# 2012_AVR.net
KiCad netlist of a schematic drawn in Altium Designer
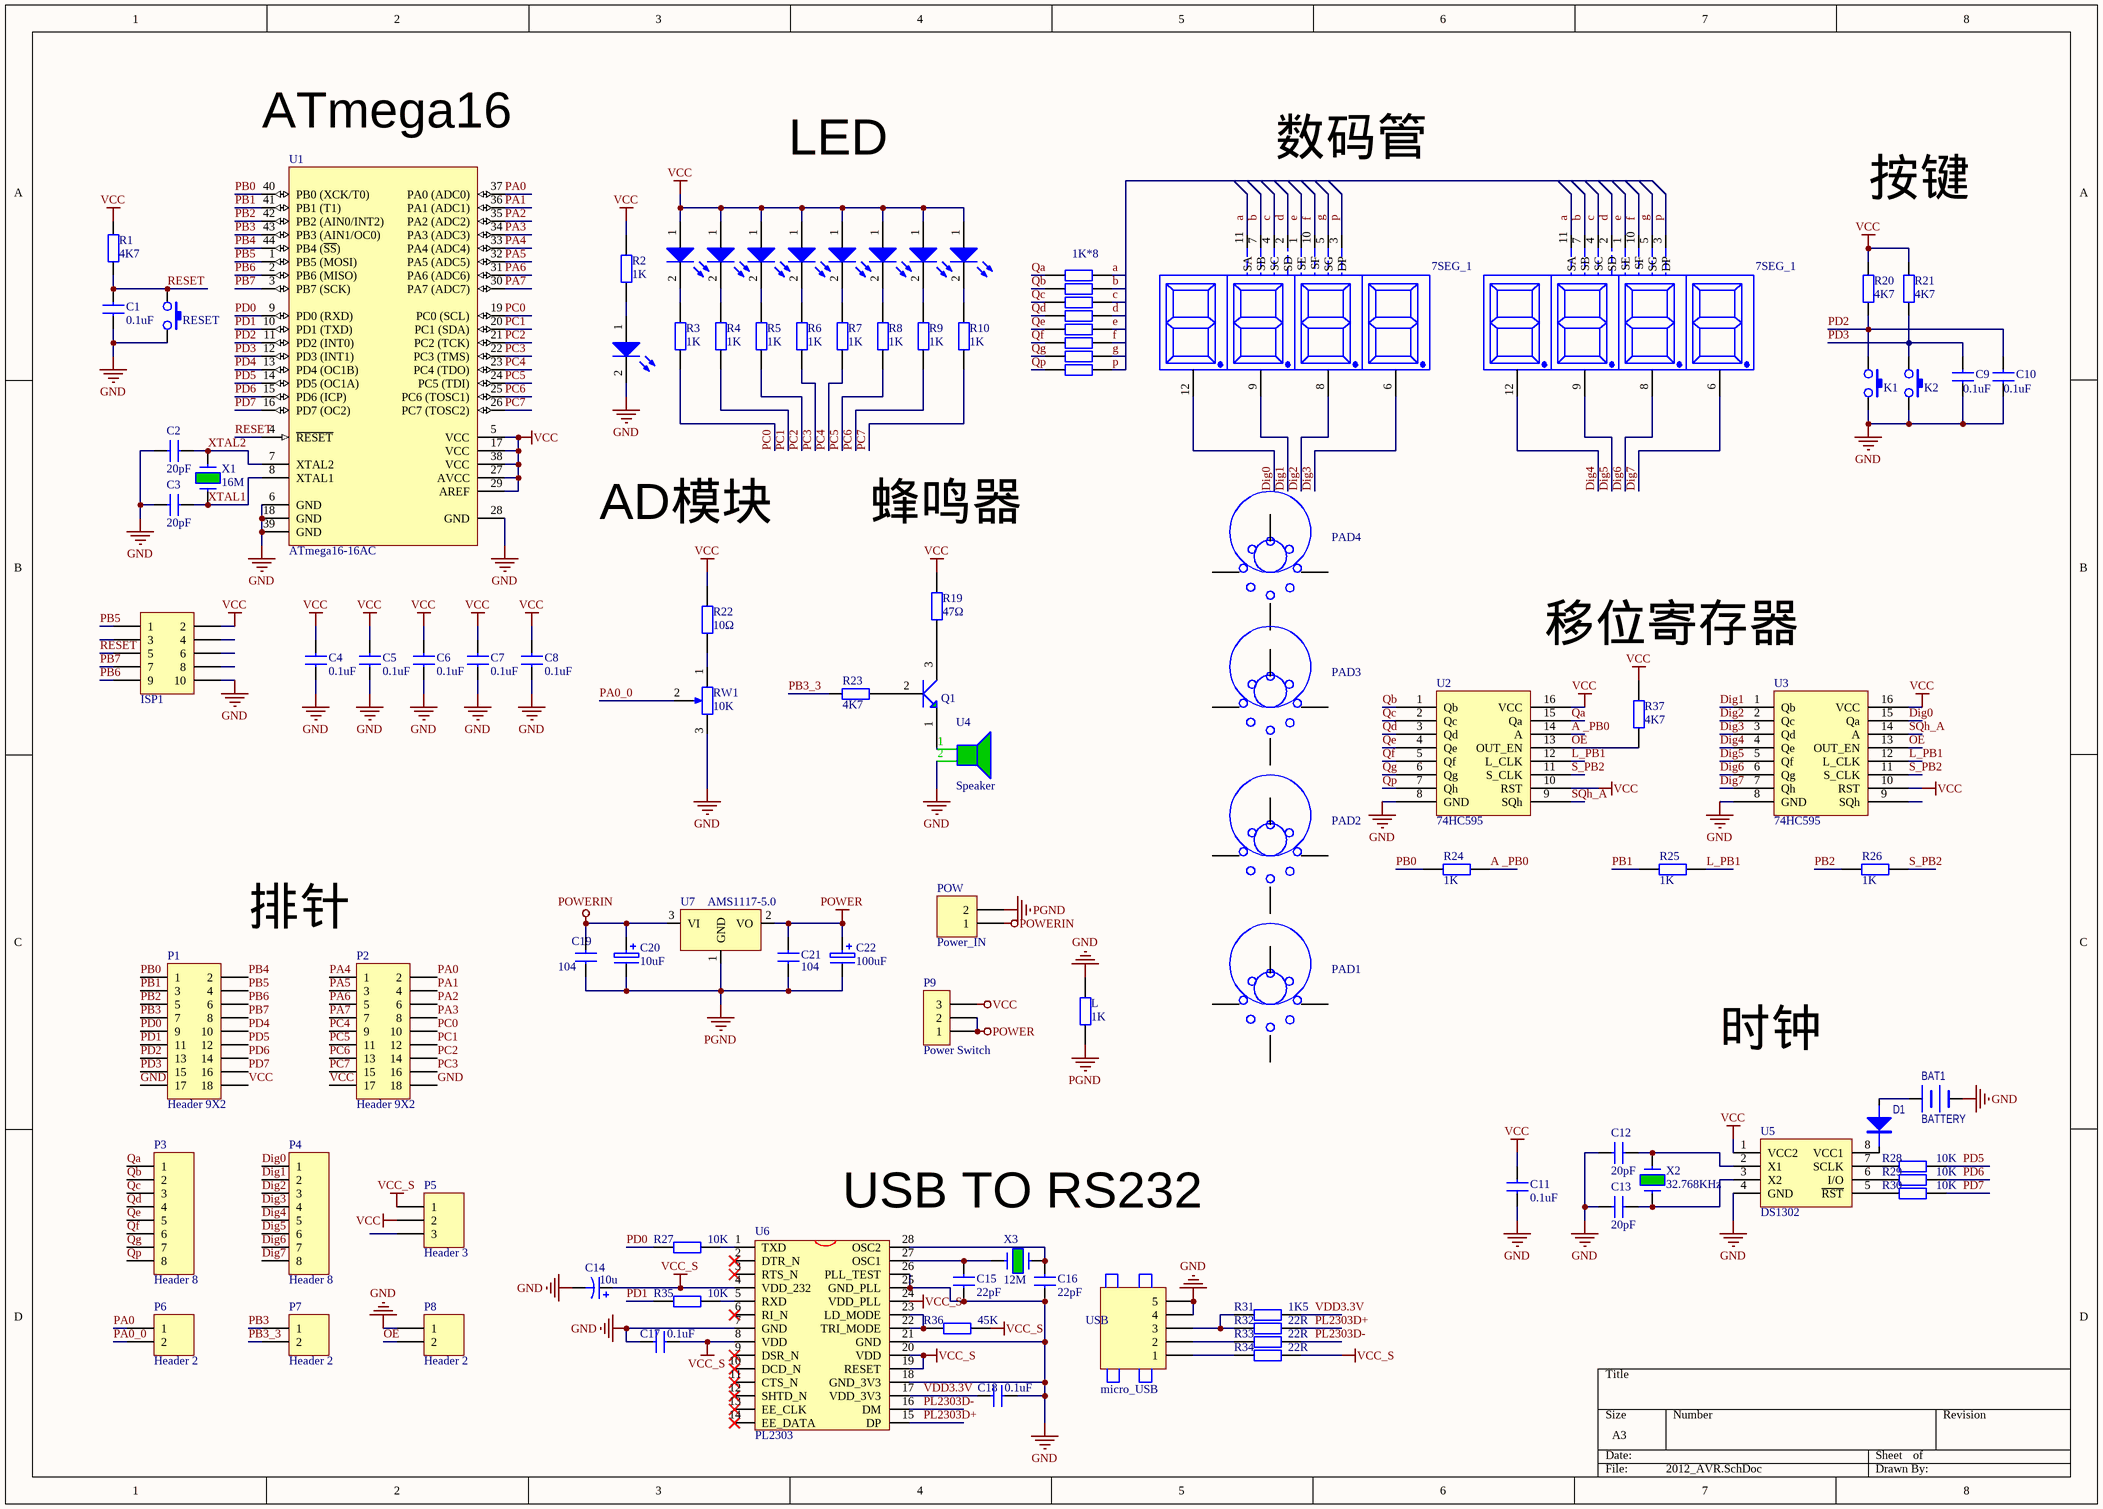
[diagram p0: 2012_AVR.SchDoc]

(export (version "E")
  (design (tool "Eeschema 10.0.6"))
  (components
    (comp (ref "1") (value "7SEG_1") (footprint "DSP-4") (libsource (lib "Free Documents") (part "四位共阴数码管")))
    (comp (ref "2") (value "7SEG_1") (footprint "DSP-4") (libsource (lib "Free Documents") (part "四位共阴数码管")))
    (comp (ref "BAT1")
      (value "BATTERY")
      (footprint "BAT600")
      (libsource (lib "Free Documents") (part "BATTERY"))
    )
    (comp (ref "C1")
      (value "0.1uF")
      (footprint "C0704")
      (description "Capacitor")
      (libsource (lib "Free Documents") (part "CAP"))
    )
    (comp (ref "C2")
      (value "20pF")
      (footprint "C0704")
      (description "Capacitor")
      (libsource (lib "Free Documents") (part "CAP"))
    )
    (comp (ref "C3")
      (value "20pF")
      (footprint "C0704")
      (description "Capacitor")
      (libsource (lib "Free Documents") (part "CAP"))
    )
    (comp (ref "C4")
      (value "0.1uF")
      (footprint "C0704")
      (description "Capacitor")
      (libsource (lib "Free Documents") (part "CAP"))
    )
    (comp (ref "C5")
      (value "0.1uF")
      (footprint "C0704")
      (description "Capacitor")
      (libsource (lib "Free Documents") (part "CAP"))
    )
    (comp (ref "C6")
      (value "0.1uF")
      (footprint "C0704")
      (description "Capacitor")
      (libsource (lib "Free Documents") (part "CAP"))
    )
    (comp (ref "C7")
      (value "0.1uF")
      (footprint "C0704")
      (description "Capacitor")
      (libsource (lib "Free Documents") (part "CAP"))
    )
    (comp (ref "C8")
      (value "0.1uF")
      (footprint "C0704")
      (description "Capacitor")
      (libsource (lib "Free Documents") (part "CAP"))
    )
    (comp (ref "C9")
      (value "0.1uF")
      (footprint "C0704")
      (description "Capacitor")
      (libsource (lib "Free Documents") (part "CAP"))
    )
    (comp (ref "C10")
      (value "0.1uF")
      (footprint "C0704")
      (description "Capacitor")
      (libsource (lib "Free Documents") (part "CAP"))
    )
    (comp (ref "C11")
      (value "0.1uF")
      (footprint "C0704")
      (description "Capacitor")
      (libsource (lib "Free Documents") (part "CAP"))
    )
    (comp (ref "C12")
      (value "20pF")
      (footprint "C0704")
      (description "Capacitor")
      (libsource (lib "Free Documents") (part "CAP"))
    )
    (comp (ref "C13")
      (value "20pF")
      (footprint "C0704")
      (description "Capacitor")
      (libsource (lib "Free Documents") (part "CAP"))
    )
    (comp (ref "C14")
      (value "10u")
      (footprint "3216C")
      (description "Polarized Capacitor (Radial)")
      (fields (field (name "Comment") "Cap Pol1"))
      (libsource (lib "Free Documents") (part "Cap Pol1"))
    )
    (comp (ref "C15")
      (value "22pF")
      (footprint "C0704")
      (description "Capacitor")
      (libsource (lib "Free Documents") (part "CAP"))
    )
    (comp (ref "C16")
      (value "22pF")
      (footprint "C0704")
      (description "Capacitor")
      (libsource (lib "Free Documents") (part "CAP"))
    )
    (comp (ref "C17")
      (value "0.1uF")
      (footprint "C0704")
      (description "Capacitor")
      (libsource (lib "Free Documents") (part "CAP"))
    )
    (comp (ref "C18")
      (value "0.1uF")
      (footprint "C0704")
      (description "Capacitor")
      (libsource (lib "Free Documents") (part "CAP"))
    )
    (comp (ref "C19")
      (value "104")
      (footprint "0805")
      (description "Capacitor")
      (libsource (lib "*") (part "CAP"))
    )
    (comp (ref "C20")
      (value "10uF")
      (footprint "3216C")
      (description "Electrolytic Capacitor")
      (libsource (lib "*") (part "ELECTRO"))
    )
    (comp (ref "C21")
      (value "104")
      (footprint "0805")
      (description "Capacitor")
      (libsource (lib "*") (part "CAP"))
    )
    (comp (ref "C22")
      (value "100uF")
      (footprint "3216C")
      (description "Electrolytic Capacitor")
      (libsource (lib "*") (part "ELECTRO"))
    )
    (comp (ref "D1") (value "1N4148") (footprint "D1206") (libsource (lib "Free Documents") (part "DIODE")))
    (comp (ref "ISP1")
      (value "ISP2*5")
      (footprint "ISP(2*5)")
      (description "Header, 5-Pin, Dual row")
      (libsource (lib "Free Documents") (part "ISP2*5"))
    )
    (comp (ref "K1")
      (value "SWITCH-PB1")
      (footprint "SW-6-6")
      (libsource (lib "Free Documents") (part "SWITCH-PB1"))
    )
    (comp (ref "K2")
      (value "SWITCH-PB1")
      (footprint "SW-6-6")
      (libsource (lib "Free Documents") (part "SWITCH-PB1"))
    )
    (comp (ref "L")
      (value "1K")
      (footprint "0805")
      (description "Resistor")
      (fields (field (name "MANUFACTURER") "Generic Components"))
      (libsource (lib "2013学习板") (part "RES"))
    )
    (comp (ref "LED0")
      (value "LED")
      (footprint "1210LED")
      (description "Typical BLUE SiC LED")
      (fields (field (name "MANUFACTURER") "Generic Components"))
      (libsource (lib "Free Documents") (part "LED"))
    )
    (comp (ref "LED1")
      (value "LED")
      (footprint "1210LED")
      (description "Typical BLUE SiC LED")
      (fields (field (name "MANUFACTURER") "Generic Components"))
      (libsource (lib "Free Documents") (part "LED"))
    )
    (comp (ref "LED2")
      (value "LED")
      (footprint "1210LED")
      (description "Typical BLUE SiC LED")
      (fields (field (name "MANUFACTURER") "Generic Components"))
      (libsource (lib "Free Documents") (part "LED"))
    )
    (comp (ref "LED3")
      (value "LED")
      (footprint "1210LED")
      (description "Typical BLUE SiC LED")
      (fields (field (name "MANUFACTURER") "Generic Components"))
      (libsource (lib "Free Documents") (part "LED"))
    )
    (comp (ref "LED4")
      (value "LED")
      (footprint "1210LED")
      (description "Typical BLUE SiC LED")
      (fields (field (name "MANUFACTURER") "Generic Components"))
      (libsource (lib "Free Documents") (part "LED"))
    )
    (comp (ref "LED5")
      (value "LED")
      (footprint "1210LED")
      (description "Typical BLUE SiC LED")
      (fields (field (name "MANUFACTURER") "Generic Components"))
      (libsource (lib "Free Documents") (part "LED"))
    )
    (comp (ref "LED6")
      (value "LED")
      (footprint "1210LED")
      (description "Typical BLUE SiC LED")
      (fields (field (name "MANUFACTURER") "Generic Components"))
      (libsource (lib "Free Documents") (part "LED"))
    )
    (comp (ref "LED7")
      (value "LED")
      (footprint "1210LED")
      (description "Typical BLUE SiC LED")
      (fields (field (name "MANUFACTURER") "Generic Components"))
      (libsource (lib "Free Documents") (part "LED"))
    )
    (comp (ref "P1")
      (value "Header 9X2")
      (footprint "HDR2X9")
      (description "Header, 9-Pin, Dual row")
      (libsource (lib "Free Documents") (part "Header 9X2"))
    )
    (comp (ref "P2")
      (value "Header 9X2")
      (footprint "HDR2X9")
      (description "Header, 9-Pin, Dual row")
      (libsource (lib "Free Documents") (part "Header 9X2"))
    )
    (comp (ref "P3")
      (value "Header 8")
      (footprint "HDR1X8")
      (description "Header, 8-Pin")
      (libsource (lib "Miscellaneous Connectors") (part "Header 8"))
    )
    (comp (ref "P4")
      (value "Header 8")
      (footprint "HDR1X8")
      (description "Header, 8-Pin")
      (libsource (lib "Miscellaneous Connectors") (part "Header 8"))
    )
    (comp (ref "P5")
      (value "Header 3")
      (footprint "HDR1X3")
      (description "Header, 3-Pin")
      (libsource (lib "L_MainBoard_V4.0") (part "Header 3"))
    )
    (comp (ref "P6")
      (value "Header 2")
      (footprint "HDR1X2")
      (description "Header, 2-Pin")
      (libsource (lib "") (part "Header 2_1"))
    )
    (comp (ref "P7")
      (value "Header 2")
      (footprint "HDR1X2")
      (description "Header, 2-Pin")
      (libsource (lib "") (part "Header 2_1"))
    )
    (comp (ref "P8")
      (value "Header 2")
      (footprint "HDR1X2")
      (description "Header, 2-Pin")
      (libsource (lib "") (part "Header 2_1"))
    )
    (comp (ref "P9")
      (value "Power Switch")
      (footprint "HDR1X3")
      (description "Connector")
      (libsource (lib "*") (part "CON3"))
    )
    (comp (ref "PAD1") (value "hotpad") (footprint "hot_pad") (libsource (lib "2012_AVR") (part "HOT_PAD")))
    (comp (ref "PAD2") (value "hotpad") (footprint "hot_pad") (libsource (lib "2012_AVR") (part "HOT_PAD")))
    (comp (ref "PAD3") (value "hotpad") (footprint "hot_pad") (libsource (lib "2012_AVR") (part "HOT_PAD")))
    (comp (ref "PAD4") (value "hotpad") (footprint "hot_pad") (libsource (lib "2012_AVR") (part "HOT_PAD")))
    (comp (ref "POW")
      (value "Power_IN")
      (footprint "BAT_PORT")
      (description "Header, 2-Pin")
      (libsource (lib "Miscellaneous Connectors") (part "Header 2"))
    )
    (comp (ref "POWER")
      (value "LED")
      (footprint "1210LED")
      (description "Typical BLUE SiC LED")
      (fields (field (name "MANUFACTURER") "Generic Components"))
      (libsource (lib "Free Documents") (part "LED"))
    )
    (comp (ref "Q1") (value "1AMNPN9013") (footprint "CHIP") (libsource (lib "Free Documents") (part "9013")))
    (comp (ref "R1")
      (value "4K7")
      (footprint "R0704")
      (description "Resistor")
      (fields (field (name "Comment") "Res2"))
      (libsource (lib "") (part "Res2_1"))
    )
    (comp (ref "R2")
      (value "1K")
      (footprint "R0704")
      (description "Resistor")
      (fields (field (name "MANUFACTURER") "Generic Components"))
      (libsource (lib "Free Documents") (part "RES"))
    )
    (comp (ref "R3")
      (value "1K")
      (footprint "R0704")
      (description "Resistor")
      (fields (field (name "MANUFACTURER") "Generic Components"))
      (libsource (lib "Free Documents") (part "RES"))
    )
    (comp (ref "R4")
      (value "1K")
      (footprint "R0704")
      (description "Resistor")
      (fields (field (name "MANUFACTURER") "Generic Components"))
      (libsource (lib "Free Documents") (part "RES"))
    )
    (comp (ref "R5")
      (value "1K")
      (footprint "R0704")
      (description "Resistor")
      (fields (field (name "MANUFACTURER") "Generic Components"))
      (libsource (lib "Free Documents") (part "RES"))
    )
    (comp (ref "R6")
      (value "1K")
      (footprint "R0704")
      (description "Resistor")
      (fields (field (name "MANUFACTURER") "Generic Components"))
      (libsource (lib "Free Documents") (part "RES"))
    )
    (comp (ref "R7")
      (value "1K")
      (footprint "R0704")
      (description "Resistor")
      (fields (field (name "MANUFACTURER") "Generic Components"))
      (libsource (lib "Free Documents") (part "RES"))
    )
    (comp (ref "R8")
      (value "1K")
      (footprint "R0704")
      (description "Resistor")
      (fields (field (name "MANUFACTURER") "Generic Components"))
      (libsource (lib "Free Documents") (part "RES"))
    )
    (comp (ref "R9")
      (value "1K")
      (footprint "R0704")
      (description "Resistor")
      (fields (field (name "MANUFACTURER") "Generic Components"))
      (libsource (lib "Free Documents") (part "RES"))
    )
    (comp (ref "R10")
      (value "1K")
      (footprint "R0704")
      (description "Resistor")
      (fields (field (name "MANUFACTURER") "Generic Components"))
      (libsource (lib "Free Documents") (part "RES"))
    )
    (comp (ref "R11")
      (value "1K*8")
      (footprint "R0704")
      (description "Resistor")
      (fields (field (name "MANUFACTURER") "Generic Components"))
      (libsource (lib "") (part "RES_2"))
    )
    (comp (ref "R12")
      (value "1K")
      (footprint "R0704")
      (description "Resistor")
      (fields (field (name "MANUFACTURER") "Generic Components"))
      (libsource (lib "") (part "RES_2"))
    )
    (comp (ref "R13")
      (value "1K")
      (footprint "R0704")
      (description "Resistor")
      (fields (field (name "MANUFACTURER") "Generic Components"))
      (libsource (lib "") (part "RES_2"))
    )
    (comp (ref "R14")
      (value "1K")
      (footprint "R0704")
      (description "Resistor")
      (fields (field (name "MANUFACTURER") "Generic Components"))
      (libsource (lib "") (part "RES_2"))
    )
    (comp (ref "R15")
      (value "1K")
      (footprint "R0704")
      (description "Resistor")
      (fields (field (name "MANUFACTURER") "Generic Components"))
      (libsource (lib "") (part "RES_2"))
    )
    (comp (ref "R16")
      (value "1K")
      (footprint "R0704")
      (description "Resistor")
      (fields (field (name "MANUFACTURER") "Generic Components"))
      (libsource (lib "") (part "RES_2"))
    )
    (comp (ref "R17")
      (value "1K")
      (footprint "R0704")
      (description "Resistor")
      (fields (field (name "MANUFACTURER") "Generic Components"))
      (libsource (lib "") (part "RES_2"))
    )
    (comp (ref "R18")
      (value "1K")
      (footprint "R0704")
      (description "Resistor")
      (fields (field (name "MANUFACTURER") "Generic Components"))
      (libsource (lib "") (part "RES_2"))
    )
    (comp (ref "R19")
      (value "47Ω")
      (footprint "R0704")
      (description "Resistor")
      (fields (field (name "MANUFACTURER") "Generic Components") (field (name "Comment") "1K"))
      (libsource (lib "Free Documents") (part "RES"))
    )
    (comp (ref "R20")
      (value "4K7")
      (footprint "R0704")
      (description "Resistor")
      (fields (field (name "Comment") "Res2"))
      (libsource (lib "Free Documents") (part "Res2"))
    )
    (comp (ref "R21")
      (value "4K7")
      (footprint "R0704")
      (description "Resistor")
      (fields (field (name "Comment") "Res2"))
      (libsource (lib "Free Documents") (part "Res2"))
    )
    (comp (ref "R22")
      (value "10Ω")
      (footprint "R0704")
      (description "Resistor")
      (fields (field (name "MANUFACTURER") "Generic Components") (field (name "Comment") "1K"))
      (libsource (lib "Free Documents") (part "RES"))
    )
    (comp (ref "R23")
      (value "4K7")
      (footprint "R0704")
      (description "Resistor")
      (fields (field (name "Comment") "Res2"))
      (libsource (lib "") (part "Res2_2"))
    )
    (comp (ref "R24")
      (value "1K")
      (footprint "R0704")
      (description "Resistor")
      (fields (field (name "MANUFACTURER") "Generic Components"))
      (libsource (lib "") (part "RES_1"))
    )
    (comp (ref "R25")
      (value "1K")
      (footprint "R0704")
      (description "Resistor")
      (fields (field (name "MANUFACTURER") "Generic Components"))
      (libsource (lib "") (part "RES_1"))
    )
    (comp (ref "R26")
      (value "1K")
      (footprint "R0704")
      (description "Resistor")
      (fields (field (name "MANUFACTURER") "Generic Components"))
      (libsource (lib "") (part "RES_1"))
    )
    (comp (ref "R27")
      (value "10K")
      (footprint "R0704")
      (description "Resistor")
      (fields (field (name "MANUFACTURER") "Generic Components") (field (name "Comment") "20"))
      (libsource (lib "") (part "RES_1"))
    )
    (comp (ref "R28")
      (value "10K")
      (footprint "R0704")
      (description "Resistor")
      (fields (field (name "MANUFACTURER") "Generic Components") (field (name "Comment") "1K"))
      (libsource (lib "") (part "RES_1"))
    )
    (comp (ref "R29")
      (value "10K")
      (footprint "R0704")
      (description "Resistor")
      (fields (field (name "MANUFACTURER") "Generic Components") (field (name "Comment") "1K"))
      (libsource (lib "") (part "RES_1"))
    )
    (comp (ref "R30")
      (value "10K")
      (footprint "R0704")
      (description "Resistor")
      (fields (field (name "MANUFACTURER") "Generic Components") (field (name "Comment") "1K"))
      (libsource (lib "") (part "RES_1"))
    )
    (comp (ref "R31")
      (value "1K5")
      (footprint "R0704")
      (description "Resistor")
      (fields (field (name "MANUFACTURER") "Generic Components") (field (name "Comment") "1K"))
      (libsource (lib "") (part "RES_2"))
    )
    (comp (ref "R32")
      (value "22R")
      (footprint "R0704")
      (description "Resistor")
      (fields (field (name "MANUFACTURER") "Generic Components") (field (name "Comment") "1K"))
      (libsource (lib "") (part "RES_1"))
    )
    (comp (ref "R33")
      (value "22R")
      (footprint "R0704")
      (description "Resistor")
      (fields (field (name "MANUFACTURER") "Generic Components") (field (name "Comment") "1K"))
      (libsource (lib "") (part "RES_1"))
    )
    (comp (ref "R34")
      (value "22R")
      (footprint "R0704")
      (description "Resistor")
      (fields (field (name "MANUFACTURER") "Generic Components"))
      (libsource (lib "") (part "RES_1"))
    )
    (comp (ref "R35")
      (value "10K")
      (footprint "R0704")
      (description "Resistor")
      (fields (field (name "MANUFACTURER") "Generic Components") (field (name "Comment") "1K"))
      (libsource (lib "") (part "RES_1"))
    )
    (comp (ref "R36")
      (value "45K")
      (footprint "R0704")
      (description "Resistor")
      (fields (field (name "MANUFACTURER") "Generic Components") (field (name "Comment") "1K"))
      (libsource (lib "") (part "RES_1"))
    )
    (comp (ref "R37")
      (value "4K7")
      (footprint "R0704")
      (description "Resistor")
      (fields (field (name "MANUFACTURER") "Generic Components") (field (name "Comment") "1K"))
      (libsource (lib "Free Documents") (part "RES"))
    )
    (comp (ref "RESET")
      (value "SWITCH-PB1")
      (footprint "SW-6-6")
      (libsource (lib "Free Documents") (part "SWITCH-PB1"))
    )
    (comp (ref "RW1")
      (value "10K")
      (footprint "RW")
      (description "Potentiometer")
      (fields (field (name "MANUFACTURER") "Generic Components") (field (name "Comment") "RPOT"))
      (libsource (lib "Free Documents") (part "RPOT"))
    )
    (comp (ref "U1")
      (value "ATmega16-16AC")
      (footprint "mega16 tie")
      (description "8-Bit AVR Microcontroller with 16K Bytes of In-System Programmable Flash Memory")
      (libsource (lib "Free Documents") (part "ATmega16-16AC"))
    )
    (comp (ref "U2")
      (value "74HC595")
      (footprint "SOP16")
      (libsource (lib "Free Documents") (part "74HC595_1"))
    )
    (comp (ref "U3")
      (value "74HC595")
      (footprint "SOP16")
      (libsource (lib "Free Documents") (part "74HC595_1"))
    )
    (comp (ref "U4")
      (value "Speaker")
      (footprint "SPEAKER")
      (libsource (lib "Free Documents") (part "Speaker"))
    )
    (comp (ref "U5") (value "DS1302") (footprint "SO-8") (libsource (lib "Free Documents") (part "DS1302")))
    (comp (ref "U6") (value "PL2303") (footprint "ssop28") (libsource (lib "Free Documents") (part "PL2303")))
    (comp (ref "U7") (value "AMS1117-5.0") (footprint "DSO-G3") (libsource (lib "*") (part "AS1117")))
    (comp (ref "USB")
      (value "micro_USB")
      (footprint "USBfoot")
      (description "手机用")
      (libsource (lib "2013_AVR_V1.0") (part "micro_USB"))
    )
    (comp (ref "X1")
      (value "16M")
      (footprint "XTAL")
      (description "Crystal")
      (libsource (lib "Free Documents") (part "CRYSTAL"))
    )
    (comp (ref "X2")
      (value "32.768KHz")
      (footprint "XTAL-B")
      (description "Crystal")
      (libsource (lib "Free Documents") (part "CRYSTAL_1"))
    )
    (comp (ref "X3")
      (value "12M")
      (footprint "XTAL")
      (description "Crystal")
      (libsource (lib "Free Documents") (part "CRYSTAL"))
    )
  )
  (nets
    (net (code "1") (name "/A _PB0") (class "Default")
      (node (ref "R24") (pin "1") (pinfunction "1_1") (pintype "passive"))
      (node (ref "U2") (pin "14") (pinfunction "A_14") (pintype "passive"))
    )
    (net (code "2") (name "/Dig0") (class "Default")
      (node (ref "1") (pin "12") (pinfunction "GID4_12") (pintype "passive"))
      (node (ref "P4") (pin "1") (pinfunction "1_1") (pintype "passive"))
      (node (ref "U3") (pin "15") (pinfunction "Qa_15") (pintype "passive"))
    )
    (net (code "3") (name "/Dig1") (class "Default")
      (node (ref "1") (pin "9") (pinfunction "DIG3_9") (pintype "passive"))
      (node (ref "P4") (pin "2") (pinfunction "2_2") (pintype "passive"))
      (node (ref "U3") (pin "1") (pinfunction "Qb_1") (pintype "passive"))
    )
    (net (code "4") (name "/Dig2") (class "Default")
      (node (ref "1") (pin "8") (pinfunction "DIG2_8") (pintype "passive"))
      (node (ref "P4") (pin "3") (pinfunction "3_3") (pintype "passive"))
      (node (ref "U3") (pin "2") (pinfunction "Qc_2") (pintype "passive"))
    )
    (net (code "5") (name "/Dig3") (class "Default")
      (node (ref "1") (pin "6") (pinfunction "GIG1_6") (pintype "passive"))
      (node (ref "P4") (pin "4") (pinfunction "4_4") (pintype "passive"))
      (node (ref "U3") (pin "3") (pinfunction "Qd_3") (pintype "passive"))
    )
    (net (code "6") (name "/Dig4") (class "Default")
      (node (ref "2") (pin "12") (pinfunction "GID4_12") (pintype "passive"))
      (node (ref "P4") (pin "5") (pinfunction "5_5") (pintype "passive"))
      (node (ref "U3") (pin "4") (pinfunction "Qe_4") (pintype "passive"))
    )
    (net (code "7") (name "/Dig5") (class "Default")
      (node (ref "2") (pin "9") (pinfunction "DIG3_9") (pintype "passive"))
      (node (ref "P4") (pin "6") (pinfunction "6_6") (pintype "passive"))
      (node (ref "U3") (pin "5") (pinfunction "Qf_5") (pintype "passive"))
    )
    (net (code "8") (name "/Dig6") (class "Default")
      (node (ref "2") (pin "8") (pinfunction "DIG2_8") (pintype "passive"))
      (node (ref "P4") (pin "7") (pinfunction "7_7") (pintype "passive"))
      (node (ref "U3") (pin "6") (pinfunction "Qg_6") (pintype "passive"))
    )
    (net (code "9") (name "/Dig7") (class "Default")
      (node (ref "2") (pin "6") (pinfunction "GIG1_6") (pintype "passive"))
      (node (ref "P4") (pin "8") (pinfunction "8_8") (pintype "passive"))
      (node (ref "U3") (pin "7") (pinfunction "Qh_7") (pintype "passive"))
    )
    (net (code "10") (name "/L_PB1") (class "Default")
      (node (ref "R25") (pin "1") (pinfunction "1_1") (pintype "passive"))
      (node (ref "U2") (pin "12") (pinfunction "L_CLK_12") (pintype "passive"))
      (node (ref "U3") (pin "12") (pinfunction "L_CLK_12") (pintype "passive"))
    )
    (net (code "11") (name "/OE") (class "Default")
      (node (ref "P8") (pin "2") (pinfunction "2_2") (pintype "passive"))
      (node (ref "R37") (pin "2") (pinfunction "2_2") (pintype "passive"))
      (node (ref "U2") (pin "13") (pinfunction "OUT_EN_13") (pintype "passive"))
      (node (ref "U3") (pin "13") (pinfunction "OUT_EN_13") (pintype "passive"))
    )
    (net (code "12") (name "/PA0") (class "Default")
      (node (ref "P2") (pin "2") (pinfunction "2_2") (pintype "passive"))
      (node (ref "P6") (pin "1") (pinfunction "1_1") (pintype "passive"))
      (node (ref "U1") (pin "37") (pinfunction "PA0_(ADC0)_37") (pintype "bidirectional"))
    )
    (net (code "13") (name "/PA0_0") (class "Default")
      (node (ref "P6") (pin "2") (pinfunction "2_2") (pintype "passive"))
      (node (ref "RW1") (pin "2") (pinfunction "2_2") (pintype "passive"))
    )
    (net (code "14") (name "/PA1") (class "Default")
      (node (ref "P2") (pin "4") (pinfunction "4_4") (pintype "passive"))
      (node (ref "U1") (pin "36") (pinfunction "PA1_(ADC1)_36") (pintype "bidirectional"))
    )
    (net (code "15") (name "/PA2") (class "Default")
      (node (ref "P2") (pin "6") (pinfunction "6_6") (pintype "passive"))
      (node (ref "U1") (pin "35") (pinfunction "PA2_(ADC2)_35") (pintype "bidirectional"))
    )
    (net (code "16") (name "/PA3") (class "Default")
      (node (ref "P2") (pin "8") (pinfunction "8_8") (pintype "passive"))
      (node (ref "U1") (pin "34") (pinfunction "PA3_(ADC3)_34") (pintype "bidirectional"))
    )
    (net (code "17") (name "/PA4") (class "Default")
      (node (ref "P2") (pin "1") (pinfunction "1_1") (pintype "passive"))
      (node (ref "U1") (pin "33") (pinfunction "PA4_(ADC4)_33") (pintype "bidirectional"))
    )
    (net (code "18") (name "/PA5") (class "Default")
      (node (ref "P2") (pin "3") (pinfunction "3_3") (pintype "passive"))
      (node (ref "U1") (pin "32") (pinfunction "PA5_(ADC5)_32") (pintype "bidirectional"))
    )
    (net (code "19") (name "/PA6") (class "Default")
      (node (ref "P2") (pin "5") (pinfunction "5_5") (pintype "passive"))
      (node (ref "U1") (pin "31") (pinfunction "PA6_(ADC6)_31") (pintype "bidirectional"))
    )
    (net (code "20") (name "/PA7") (class "Default")
      (node (ref "P2") (pin "7") (pinfunction "7_7") (pintype "passive"))
      (node (ref "U1") (pin "30") (pinfunction "PA7_(ADC7)_30") (pintype "bidirectional"))
    )
    (net (code "21") (name "/PB0") (class "Default")
      (node (ref "P1") (pin "1") (pinfunction "1_1") (pintype "passive"))
      (node (ref "R24") (pin "2") (pinfunction "2_2") (pintype "passive"))
      (node (ref "U1") (pin "40") (pinfunction "PB0_(XCK/T0)_40") (pintype "bidirectional"))
    )
    (net (code "22") (name "/PB1") (class "Default")
      (node (ref "P1") (pin "3") (pinfunction "3_3") (pintype "passive"))
      (node (ref "R25") (pin "2") (pinfunction "2_2") (pintype "passive"))
      (node (ref "U1") (pin "41") (pinfunction "PB1_(T1)_41") (pintype "bidirectional"))
    )
    (net (code "23") (name "/PB2") (class "Default")
      (node (ref "P1") (pin "5") (pinfunction "5_5") (pintype "passive"))
      (node (ref "R26") (pin "2") (pinfunction "2_2") (pintype "passive"))
      (node (ref "U1") (pin "42") (pinfunction "PB2_(AIN0/INT2)_42") (pintype "bidirectional"))
    )
    (net (code "24") (name "/PB3") (class "Default")
      (node (ref "P1") (pin "7") (pinfunction "7_7") (pintype "passive"))
      (node (ref "P7") (pin "1") (pinfunction "1_1") (pintype "passive"))
      (node (ref "U1") (pin "43") (pinfunction "PB3_(AIN1/OC0)_43") (pintype "bidirectional"))
    )
    (net (code "25") (name "/PB3_3") (class "Default")
      (node (ref "P7") (pin "2") (pinfunction "2_2") (pintype "passive"))
      (node (ref "R23") (pin "2") (pinfunction "2_2") (pintype "passive"))
    )
    (net (code "26") (name "/PB4") (class "Default")
      (node (ref "P1") (pin "2") (pinfunction "2_2") (pintype "passive"))
      (node (ref "U1") (pin "44") (pinfunction "PB4_(~{SS})_44") (pintype "bidirectional"))
    )
    (net (code "27") (name "/PB5") (class "Default")
      (node (ref "ISP1") (pin "1") (pinfunction "1_1") (pintype "passive"))
      (node (ref "P1") (pin "4") (pinfunction "4_4") (pintype "passive"))
      (node (ref "U1") (pin "1") (pinfunction "PB5_(MOSI)_1") (pintype "bidirectional"))
    )
    (net (code "28") (name "/PB6") (class "Default")
      (node (ref "ISP1") (pin "9") (pinfunction "9_9") (pintype "passive"))
      (node (ref "P1") (pin "6") (pinfunction "6_6") (pintype "passive"))
      (node (ref "U1") (pin "2") (pinfunction "PB6_(MISO)_2") (pintype "bidirectional"))
    )
    (net (code "29") (name "/PB7") (class "Default")
      (node (ref "ISP1") (pin "7") (pinfunction "7_7") (pintype "passive"))
      (node (ref "P1") (pin "8") (pinfunction "8_8") (pintype "passive"))
      (node (ref "U1") (pin "3") (pinfunction "PB7_(SCK)_3") (pintype "bidirectional"))
    )
    (net (code "30") (name "/PC0") (class "Default")
      (node (ref "P2") (pin "10") (pinfunction "10_10") (pintype "passive"))
      (node (ref "R3") (pin "2") (pinfunction "2_2") (pintype "passive"))
      (node (ref "U1") (pin "19") (pinfunction "PC0_(SCL)_19") (pintype "bidirectional"))
    )
    (net (code "31") (name "/PC1") (class "Default")
      (node (ref "P2") (pin "12") (pinfunction "12_12") (pintype "passive"))
      (node (ref "R4") (pin "2") (pinfunction "2_2") (pintype "passive"))
      (node (ref "U1") (pin "20") (pinfunction "PC1_(SDA)_20") (pintype "bidirectional"))
    )
    (net (code "32") (name "/PC2") (class "Default")
      (node (ref "P2") (pin "14") (pinfunction "14_14") (pintype "passive"))
      (node (ref "R5") (pin "2") (pinfunction "2_2") (pintype "passive"))
      (node (ref "U1") (pin "21") (pinfunction "PC2_(TCK)_21") (pintype "bidirectional"))
    )
    (net (code "33") (name "/PC3") (class "Default")
      (node (ref "P2") (pin "16") (pinfunction "16_16") (pintype "passive"))
      (node (ref "R6") (pin "2") (pinfunction "2_2") (pintype "passive"))
      (node (ref "U1") (pin "22") (pinfunction "PC3_(TMS)_22") (pintype "bidirectional"))
    )
    (net (code "34") (name "/PC4") (class "Default")
      (node (ref "P2") (pin "9") (pinfunction "9_9") (pintype "passive"))
      (node (ref "R7") (pin "2") (pinfunction "2_2") (pintype "passive"))
      (node (ref "U1") (pin "23") (pinfunction "PC4_(TDO)_23") (pintype "bidirectional"))
    )
    (net (code "35") (name "/PC5") (class "Default")
      (node (ref "P2") (pin "11") (pinfunction "11_11") (pintype "passive"))
      (node (ref "R8") (pin "2") (pinfunction "2_2") (pintype "passive"))
      (node (ref "U1") (pin "24") (pinfunction "PC5_(TDI)_24") (pintype "bidirectional"))
    )
    (net (code "36") (name "/PC6") (class "Default")
      (node (ref "P2") (pin "13") (pinfunction "13_13") (pintype "passive"))
      (node (ref "R9") (pin "2") (pinfunction "2_2") (pintype "passive"))
      (node (ref "U1") (pin "25") (pinfunction "PC6_(TOSC1)_25") (pintype "bidirectional"))
    )
    (net (code "37") (name "/PC7") (class "Default")
      (node (ref "P2") (pin "15") (pinfunction "15_15") (pintype "passive"))
      (node (ref "R10") (pin "2") (pinfunction "2_2") (pintype "passive"))
      (node (ref "U1") (pin "26") (pinfunction "PC7_(TOSC2)_26") (pintype "bidirectional"))
    )
    (net (code "38") (name "/PD0") (class "Default")
      (node (ref "P1") (pin "9") (pinfunction "9_9") (pintype "passive"))
      (node (ref "R27") (pin "2") (pinfunction "2_2") (pintype "passive"))
      (node (ref "U1") (pin "9") (pinfunction "PD0_(RXD)_9") (pintype "bidirectional"))
    )
    (net (code "39") (name "/PD1") (class "Default")
      (node (ref "P1") (pin "11") (pinfunction "11_11") (pintype "passive"))
      (node (ref "R35") (pin "2") (pinfunction "2_2") (pintype "passive"))
      (node (ref "U1") (pin "10") (pinfunction "PD1_(TXD)_10") (pintype "bidirectional"))
    )
    (net (code "40") (name "/PD2") (class "Default")
      (node (ref "C10") (pin "2") (pinfunction "2_2") (pintype "passive"))
      (node (ref "K1") (pin "1") (pinfunction "1_1") (pintype "passive"))
      (node (ref "P1") (pin "13") (pinfunction "13_13") (pintype "passive"))
      (node (ref "R20") (pin "2") (pinfunction "2_2") (pintype "passive"))
      (node (ref "U1") (pin "11") (pinfunction "PD2_(INT0)_11") (pintype "bidirectional"))
    )
    (net (code "41") (name "/PD3") (class "Default")
      (node (ref "C9") (pin "2") (pinfunction "2_2") (pintype "passive"))
      (node (ref "K2") (pin "1") (pinfunction "1_1") (pintype "passive"))
      (node (ref "P1") (pin "15") (pinfunction "15_15") (pintype "passive"))
      (node (ref "R21") (pin "2") (pinfunction "2_2") (pintype "passive"))
      (node (ref "U1") (pin "12") (pinfunction "PD3_(INT1)_12") (pintype "bidirectional"))
    )
    (net (code "42") (name "/PD4") (class "Default")
      (node (ref "P1") (pin "10") (pinfunction "10_10") (pintype "passive"))
      (node (ref "U1") (pin "13") (pinfunction "PD4_(OC1B)_13") (pintype "bidirectional"))
    )
    (net (code "43") (name "/PD5") (class "Default")
      (node (ref "P1") (pin "12") (pinfunction "12_12") (pintype "passive"))
      (node (ref "R28") (pin "1") (pinfunction "1_1") (pintype "passive"))
      (node (ref "U1") (pin "14") (pinfunction "PD5_(OC1A)_14") (pintype "bidirectional"))
    )
    (net (code "44") (name "/PD6") (class "Default")
      (node (ref "P1") (pin "14") (pinfunction "14_14") (pintype "passive"))
      (node (ref "R29") (pin "1") (pinfunction "1_1") (pintype "passive"))
      (node (ref "U1") (pin "15") (pinfunction "PD6_(ICP)_15") (pintype "bidirectional"))
    )
    (net (code "45") (name "/PD7") (class "Default")
      (node (ref "P1") (pin "16") (pinfunction "16_16") (pintype "passive"))
      (node (ref "R30") (pin "1") (pinfunction "1_1") (pintype "passive"))
      (node (ref "U1") (pin "16") (pinfunction "PD7_(OC2)_16") (pintype "bidirectional"))
    )
    (net (code "46") (name "/PL2303D+") (class "Default")
      (node (ref "R32") (pin "1") (pinfunction "1_1") (pintype "passive"))
      (node (ref "U6") (pin "15") (pinfunction "DP_15") (pintype "passive"))
    )
    (net (code "47") (name "/PL2303D-") (class "Default")
      (node (ref "R33") (pin "1") (pinfunction "1_1") (pintype "passive"))
      (node (ref "U6") (pin "16") (pinfunction "DM_16") (pintype "passive"))
    )
    (net (code "48") (name "/Qa") (class "Default")
      (node (ref "P3") (pin "1") (pinfunction "1_1") (pintype "passive"))
      (node (ref "R11") (pin "1") (pinfunction "1_1") (pintype "passive"))
      (node (ref "U2") (pin "15") (pinfunction "Qa_15") (pintype "passive"))
    )
    (net (code "49") (name "/Qb") (class "Default")
      (node (ref "P3") (pin "2") (pinfunction "2_2") (pintype "passive"))
      (node (ref "R12") (pin "1") (pinfunction "1_1") (pintype "passive"))
      (node (ref "U2") (pin "1") (pinfunction "Qb_1") (pintype "passive"))
    )
    (net (code "50") (name "/Qc") (class "Default")
      (node (ref "P3") (pin "3") (pinfunction "3_3") (pintype "passive"))
      (node (ref "R13") (pin "1") (pinfunction "1_1") (pintype "passive"))
      (node (ref "U2") (pin "2") (pinfunction "Qc_2") (pintype "passive"))
    )
    (net (code "51") (name "/Qd") (class "Default")
      (node (ref "P3") (pin "4") (pinfunction "4_4") (pintype "passive"))
      (node (ref "R14") (pin "1") (pinfunction "1_1") (pintype "passive"))
      (node (ref "U2") (pin "3") (pinfunction "Qd_3") (pintype "passive"))
    )
    (net (code "52") (name "/Qe") (class "Default")
      (node (ref "P3") (pin "5") (pinfunction "5_5") (pintype "passive"))
      (node (ref "R15") (pin "1") (pinfunction "1_1") (pintype "passive"))
      (node (ref "U2") (pin "4") (pinfunction "Qe_4") (pintype "passive"))
    )
    (net (code "53") (name "/Qf") (class "Default")
      (node (ref "P3") (pin "6") (pinfunction "6_6") (pintype "passive"))
      (node (ref "R16") (pin "1") (pinfunction "1_1") (pintype "passive"))
      (node (ref "U2") (pin "5") (pinfunction "Qf_5") (pintype "passive"))
    )
    (net (code "54") (name "/Qg") (class "Default")
      (node (ref "P3") (pin "7") (pinfunction "7_7") (pintype "passive"))
      (node (ref "R17") (pin "1") (pinfunction "1_1") (pintype "passive"))
      (node (ref "U2") (pin "6") (pinfunction "Qg_6") (pintype "passive"))
    )
    (net (code "55") (name "/Qp") (class "Default")
      (node (ref "P3") (pin "8") (pinfunction "8_8") (pintype "passive"))
      (node (ref "R18") (pin "1") (pinfunction "1_1") (pintype "passive"))
      (node (ref "U2") (pin "7") (pinfunction "Qh_7") (pintype "passive"))
    )
    (net (code "56") (name "/RESET") (class "Default")
      (node (ref "C1") (pin "1") (pinfunction "1_1") (pintype "passive"))
      (node (ref "ISP1") (pin "5") (pinfunction "5_5") (pintype "passive"))
      (node (ref "R1") (pin "1") (pinfunction "1_1") (pintype "passive"))
      (node (ref "RESET") (pin "1") (pinfunction "1_1") (pintype "passive"))
      (node (ref "U1") (pin "4") (pinfunction "~{RESET}_4") (pintype "input"))
    )
    (net (code "57") (name "/SQh_A") (class "Default")
      (node (ref "U2") (pin "9") (pinfunction "SQh_9") (pintype "passive"))
      (node (ref "U3") (pin "14") (pinfunction "A_14") (pintype "passive"))
    )
    (net (code "58") (name "/S_PB2") (class "Default")
      (node (ref "R26") (pin "1") (pinfunction "1_1") (pintype "passive"))
      (node (ref "U2") (pin "11") (pinfunction "S_CLK_11") (pintype "passive"))
      (node (ref "U3") (pin "11") (pinfunction "S_CLK_11") (pintype "passive"))
    )
    (net (code "59") (name "/VDD3.3V") (class "Default")
      (node (ref "C18") (pin "2") (pinfunction "2_2") (pintype "passive"))
      (node (ref "R31") (pin "2") (pinfunction "2_2") (pintype "passive"))
      (node (ref "U6") (pin "17") (pinfunction "VDD_3V3_17") (pintype "passive"))
    )
    (net (code "60") (name "/XTAL1") (class "Default")
      (node (ref "C3") (pin "2") (pinfunction "2_2") (pintype "passive"))
      (node (ref "U1") (pin "8") (pinfunction "XTAL1_8") (pintype "passive"))
      (node (ref "X1") (pin "1") (pinfunction "1_1") (pintype "passive"))
    )
    (net (code "61") (name "/XTAL2") (class "Default")
      (node (ref "C2") (pin "2") (pinfunction "2_2") (pintype "passive"))
      (node (ref "U1") (pin "7") (pinfunction "XTAL2_7") (pintype "passive"))
      (node (ref "X1") (pin "2") (pinfunction "2_2") (pintype "passive"))
    )
    (net (code "62") (name "/a") (class "Default")
      (node (ref "1") (pin "11") (pinfunction "SA_11") (pintype "passive"))
      (node (ref "2") (pin "11") (pinfunction "SA_11") (pintype "passive"))
      (node (ref "R11") (pin "2") (pinfunction "2_2") (pintype "passive"))
    )
    (net (code "63") (name "/b") (class "Default")
      (node (ref "1") (pin "7") (pinfunction "SB_7") (pintype "passive"))
      (node (ref "2") (pin "7") (pinfunction "SB_7") (pintype "passive"))
      (node (ref "R12") (pin "2") (pinfunction "2_2") (pintype "passive"))
    )
    (net (code "64") (name "/c") (class "Default")
      (node (ref "1") (pin "4") (pinfunction "SC_4") (pintype "passive"))
      (node (ref "2") (pin "4") (pinfunction "SC_4") (pintype "passive"))
      (node (ref "R13") (pin "2") (pinfunction "2_2") (pintype "passive"))
    )
    (net (code "65") (name "/d") (class "Default")
      (node (ref "1") (pin "2") (pinfunction "SD_2") (pintype "passive"))
      (node (ref "2") (pin "2") (pinfunction "SD_2") (pintype "passive"))
      (node (ref "R14") (pin "2") (pinfunction "2_2") (pintype "passive"))
    )
    (net (code "66") (name "/e") (class "Default")
      (node (ref "1") (pin "1") (pinfunction "SE_1") (pintype "passive"))
      (node (ref "2") (pin "1") (pinfunction "SE_1") (pintype "passive"))
      (node (ref "R15") (pin "2") (pinfunction "2_2") (pintype "passive"))
    )
    (net (code "67") (name "/f") (class "Default")
      (node (ref "1") (pin "10") (pinfunction "SF_10") (pintype "passive"))
      (node (ref "2") (pin "10") (pinfunction "SF_10") (pintype "passive"))
      (node (ref "R16") (pin "2") (pinfunction "2_2") (pintype "passive"))
    )
    (net (code "68") (name "/g") (class "Default")
      (node (ref "1") (pin "5") (pinfunction "SG_5") (pintype "passive"))
      (node (ref "2") (pin "5") (pinfunction "SG_5") (pintype "passive"))
      (node (ref "R17") (pin "2") (pinfunction "2_2") (pintype "passive"))
    )
    (net (code "69") (name "/p") (class "Default")
      (node (ref "1") (pin "3") (pinfunction "DP_3") (pintype "passive"))
      (node (ref "2") (pin "3") (pinfunction "DP_3") (pintype "passive"))
      (node (ref "R18") (pin "2") (pinfunction "2_2") (pintype "passive"))
    )
    (net (code "70") (name "GND") (class "Default")
      (node (ref "BAT1") (pin "2") (pintype "passive"))
      (node (ref "C1") (pin "2") (pinfunction "2_2") (pintype "passive"))
      (node (ref "C10") (pin "1") (pinfunction "1_1") (pintype "passive"))
      (node (ref "C11") (pin "1") (pinfunction "1_1") (pintype "passive"))
      (node (ref "C12") (pin "1") (pinfunction "1_1") (pintype "passive"))
      (node (ref "C13") (pin "1") (pinfunction "1_1") (pintype "passive"))
      (node (ref "C14") (pin "2") (pinfunction "2_2") (pintype "passive"))
      (node (ref "C15") (pin "2") (pinfunction "2_2") (pintype "passive"))
      (node (ref "C16") (pin "2") (pinfunction "2_2") (pintype "passive"))
      (node (ref "C17") (pin "2") (pinfunction "2_2") (pintype "passive"))
      (node (ref "C18") (pin "1") (pinfunction "1_1") (pintype "passive"))
      (node (ref "C2") (pin "1") (pinfunction "1_1") (pintype "passive"))
      (node (ref "C3") (pin "1") (pinfunction "1_1") (pintype "passive"))
      (node (ref "C4") (pin "1") (pinfunction "1_1") (pintype "passive"))
      (node (ref "C5") (pin "1") (pinfunction "1_1") (pintype "passive"))
      (node (ref "C6") (pin "1") (pinfunction "1_1") (pintype "passive"))
      (node (ref "C7") (pin "1") (pinfunction "1_1") (pintype "passive"))
      (node (ref "C8") (pin "1") (pinfunction "1_1") (pintype "passive"))
      (node (ref "C9") (pin "1") (pinfunction "1_1") (pintype "passive"))
      (node (ref "ISP1") (pin "10") (pinfunction "10_10") (pintype "passive"))
      (node (ref "K1") (pin "2") (pinfunction "2_2") (pintype "passive"))
      (node (ref "K2") (pin "2") (pinfunction "2_2") (pintype "passive"))
      (node (ref "L") (pin "2") (pinfunction "2_2") (pintype "passive"))
      (node (ref "P1") (pin "17") (pinfunction "17_17") (pintype "passive"))
      (node (ref "P2") (pin "18") (pinfunction "18_18") (pintype "passive"))
      (node (ref "P8") (pin "1") (pinfunction "1_1") (pintype "passive"))
      (node (ref "POWER") (pin "2") (pinfunction "2_2") (pintype "passive"))
      (node (ref "RESET") (pin "2") (pinfunction "2_2") (pintype "passive"))
      (node (ref "RW1") (pin "3") (pinfunction "3_3") (pintype "passive"))
      (node (ref "U1") (pin "18") (pinfunction "GND_18") (pintype "power_in"))
      (node (ref "U1") (pin "28") (pinfunction "GND_28") (pintype "power_in"))
      (node (ref "U1") (pin "39") (pinfunction "GND_39") (pintype "power_in"))
      (node (ref "U1") (pin "6") (pinfunction "GND_6") (pintype "power_in"))
      (node (ref "U2") (pin "8") (pinfunction "GND_8") (pintype "passive"))
      (node (ref "U3") (pin "8") (pinfunction "GND_8") (pintype "passive"))
      (node (ref "U4") (pin "2") (pinfunction "2_2") (pintype "passive"))
      (node (ref "U5") (pin "4") (pinfunction "GND_4") (pintype "passive"))
      (node (ref "U6") (pin "18") (pinfunction "GND_3V3_18") (pintype "passive"))
      (node (ref "U6") (pin "21") (pinfunction "GND_21") (pintype "passive"))
      (node (ref "U6") (pin "25") (pinfunction "GND_PLL_25") (pintype "passive"))
      (node (ref "U6") (pin "26") (pinfunction "PLL_TEST_26") (pintype "passive"))
      (node (ref "U6") (pin "7") (pinfunction "GND_7") (pintype "passive"))
      (node (ref "USB") (pin "4") (pinfunction "4_4") (pintype "passive"))
      (node (ref "USB") (pin "5") (pinfunction "5_5") (pintype "passive"))
    )
    (net (code "71") (name "Net-(BAT1-Pad1)") (class "Default")
      (node (ref "BAT1") (pin "1") (pintype "passive"))
      (node (ref "D1") (pin "1") (pinfunction "1_1") (pintype "passive"))
    )
    (net (code "72") (name "Net-(LED0-Pad2)") (class "Default")
      (node (ref "LED0") (pin "2") (pinfunction "2_2") (pintype "passive"))
      (node (ref "R3") (pin "1") (pinfunction "1_1") (pintype "passive"))
    )
    (net (code "73") (name "Net-(LED1-Pad2)") (class "Default")
      (node (ref "LED1") (pin "2") (pinfunction "2_2") (pintype "passive"))
      (node (ref "R4") (pin "1") (pinfunction "1_1") (pintype "passive"))
    )
    (net (code "74") (name "Net-(LED2-Pad2)") (class "Default")
      (node (ref "LED2") (pin "2") (pinfunction "2_2") (pintype "passive"))
      (node (ref "R5") (pin "1") (pinfunction "1_1") (pintype "passive"))
    )
    (net (code "75") (name "Net-(LED3-Pad2)") (class "Default")
      (node (ref "LED3") (pin "2") (pinfunction "2_2") (pintype "passive"))
      (node (ref "R6") (pin "1") (pinfunction "1_1") (pintype "passive"))
    )
    (net (code "76") (name "Net-(LED4-Pad2)") (class "Default")
      (node (ref "LED4") (pin "2") (pinfunction "2_2") (pintype "passive"))
      (node (ref "R7") (pin "1") (pinfunction "1_1") (pintype "passive"))
    )
    (net (code "77") (name "Net-(LED5-Pad2)") (class "Default")
      (node (ref "LED5") (pin "2") (pinfunction "2_2") (pintype "passive"))
      (node (ref "R8") (pin "1") (pinfunction "1_1") (pintype "passive"))
    )
    (net (code "78") (name "Net-(LED6-Pad2)") (class "Default")
      (node (ref "LED6") (pin "2") (pinfunction "2_2") (pintype "passive"))
      (node (ref "R9") (pin "1") (pinfunction "1_1") (pintype "passive"))
    )
    (net (code "79") (name "Net-(LED7-Pad2)") (class "Default")
      (node (ref "LED7") (pin "2") (pinfunction "2_2") (pintype "passive"))
      (node (ref "R10") (pin "1") (pinfunction "1_1") (pintype "passive"))
    )
    (net (code "80") (name "Net-(POWER-Pad1)") (class "Default")
      (node (ref "POWER") (pin "1") (pinfunction "1_1") (pintype "passive"))
      (node (ref "R2") (pin "2") (pinfunction "2_2") (pintype "passive"))
    )
    (net (code "81") (name "Net-(Q1-9)") (class "Default")
      (node (ref "Q1") (pin "2") (pinfunction "9_2") (pintype "passive"))
      (node (ref "R23") (pin "1") (pinfunction "1_1") (pintype "passive"))
    )
    (net (code "82") (name "Net-(Q1-10)") (class "Default")
      (node (ref "Q1") (pin "3") (pinfunction "10_3") (pintype "passive"))
      (node (ref "R19") (pin "2") (pinfunction "2_2") (pintype "passive"))
    )
    (net (code "83") (name "Net-(Q1-11)") (class "Default")
      (node (ref "Q1") (pin "1") (pinfunction "11_1") (pintype "passive"))
      (node (ref "U4") (pin "1") (pinfunction "1_1") (pintype "passive"))
    )
    (net (code "84") (name "Net-(R22-Pad2)") (class "Default")
      (node (ref "R22") (pin "2") (pinfunction "2_2") (pintype "passive"))
      (node (ref "RW1") (pin "1") (pinfunction "1_1") (pintype "passive"))
    )
    (net (code "85") (name "Net-(R31-Pad1)") (class "Default")
      (node (ref "R31") (pin "1") (pinfunction "1_1") (pintype "passive"))
      (node (ref "R32") (pin "2") (pinfunction "2_2") (pintype "passive"))
      (node (ref "USB") (pin "3") (pinfunction "3_3") (pintype "passive"))
    )
    (net (code "86") (name "Net-(R33-Pad2)") (class "Default")
      (node (ref "R33") (pin "2") (pinfunction "2_2") (pintype "passive"))
      (node (ref "USB") (pin "2") (pinfunction "2_2") (pintype "passive"))
    )
    (net (code "87") (name "Net-(R34-Pad2)") (class "Default")
      (node (ref "R34") (pin "2") (pinfunction "2_2") (pintype "passive"))
      (node (ref "USB") (pin "1") (pinfunction "1_1") (pintype "passive"))
    )
    (net (code "88") (name "Net-(U5-I{slash}O)") (class "Default")
      (node (ref "R29") (pin "2") (pinfunction "2_2") (pintype "passive"))
      (node (ref "U5") (pin "6") (pinfunction "I/O_6") (pintype "passive"))
    )
    (net (code "89") (name "Net-(U5-SCLK)") (class "Default")
      (node (ref "R28") (pin "2") (pinfunction "2_2") (pintype "passive"))
      (node (ref "U5") (pin "7") (pinfunction "SCLK_7") (pintype "passive"))
    )
    (net (code "90") (name "Net-(U5-VCC1)") (class "Default")
      (node (ref "D1") (pin "2") (pinfunction "2_2") (pintype "passive"))
      (node (ref "U5") (pin "8") (pinfunction "VCC1_8") (pintype "passive"))
    )
    (net (code "91") (name "Net-(U5-X1)") (class "Default")
      (node (ref "C12") (pin "2") (pinfunction "2_2") (pintype "passive"))
      (node (ref "U5") (pin "2") (pinfunction "X1_2") (pintype "passive"))
      (node (ref "X2") (pin "1") (pinfunction "1_1") (pintype "passive"))
    )
    (net (code "92") (name "Net-(U5-X2)") (class "Default")
      (node (ref "C13") (pin "2") (pinfunction "2_2") (pintype "passive"))
      (node (ref "U5") (pin "3") (pinfunction "X2_3") (pintype "passive"))
      (node (ref "X2") (pin "2") (pinfunction "2_2") (pintype "passive"))
    )
    (net (code "93") (name "Net-(U5-~{RST})") (class "Default")
      (node (ref "R30") (pin "2") (pinfunction "2_2") (pintype "passive"))
      (node (ref "U5") (pin "5") (pinfunction "~{RST}_5") (pintype "passive"))
    )
    (net (code "94") (name "Net-(U6-LD_MODE)") (class "Default")
      (node (ref "R36") (pin "2") (pinfunction "2_2") (pintype "passive"))
      (node (ref "U6") (pin "22") (pinfunction "TRI_MODE_22") (pintype "passive"))
      (node (ref "U6") (pin "23") (pinfunction "LD_MODE_23") (pintype "passive"))
    )
    (net (code "95") (name "Net-(U6-OSC1)") (class "Default")
      (node (ref "C15") (pin "1") (pinfunction "1_1") (pintype "passive"))
      (node (ref "U6") (pin "27") (pinfunction "OSC1_27") (pintype "passive"))
      (node (ref "X3") (pin "1") (pinfunction "1_1") (pintype "passive"))
    )
    (net (code "96") (name "Net-(U6-OSC2)") (class "Default")
      (node (ref "C16") (pin "1") (pinfunction "1_1") (pintype "passive"))
      (node (ref "U6") (pin "28") (pinfunction "OSC2_28") (pintype "passive"))
      (node (ref "X3") (pin "2") (pinfunction "2_2") (pintype "passive"))
    )
    (net (code "97") (name "Net-(U6-RXD)") (class "Default")
      (node (ref "R35") (pin "1") (pinfunction "1_1") (pintype "passive"))
      (node (ref "U6") (pin "5") (pinfunction "RXD_5") (pintype "passive"))
    )
    (net (code "98") (name "Net-(U6-TXD)") (class "Default")
      (node (ref "R27") (pin "1") (pinfunction "1_1") (pintype "passive"))
      (node (ref "U6") (pin "1") (pinfunction "TXD_1") (pintype "passive"))
    )
    (net (code "99") (name "PGND") (class "Default")
      (node (ref "C19") (pin "2") (pinfunction "2_2") (pintype "passive"))
      (node (ref "C20") (pin "2") (pinfunction "2_2") (pintype "passive"))
      (node (ref "C21") (pin "2") (pinfunction "2_2") (pintype "passive"))
      (node (ref "C22") (pin "2") (pinfunction "2_2") (pintype "passive"))
      (node (ref "L") (pin "1") (pinfunction "1_1") (pintype "passive"))
      (node (ref "POW") (pin "2") (pinfunction "2_2") (pintype "passive"))
      (node (ref "U7") (pin "1") (pinfunction "GND_1") (pintype "passive"))
    )
    (net (code "100") (name "POWER") (class "Default")
      (node (ref "C21") (pin "1") (pinfunction "1_1") (pintype "passive"))
      (node (ref "C22") (pin "1") (pinfunction "1_1") (pintype "passive"))
      (node (ref "P9") (pin "1") (pinfunction "1_1") (pintype "passive"))
      (node (ref "P9") (pin "2") (pinfunction "2_2") (pintype "passive"))
      (node (ref "U7") (pin "2") (pinfunction "VO_2") (pintype "passive"))
    )
    (net (code "101") (name "POWERIN") (class "Default")
      (node (ref "C19") (pin "1") (pinfunction "1_1") (pintype "passive"))
      (node (ref "C20") (pin "1") (pinfunction "1_1") (pintype "passive"))
      (node (ref "POW") (pin "1") (pinfunction "1_1") (pintype "passive"))
      (node (ref "U7") (pin "3") (pinfunction "VI_3") (pintype "passive"))
    )
    (net (code "102") (name "VCC") (class "Default")
      (node (ref "C11") (pin "2") (pinfunction "2_2") (pintype "passive"))
      (node (ref "C4") (pin "2") (pinfunction "2_2") (pintype "passive"))
      (node (ref "C5") (pin "2") (pinfunction "2_2") (pintype "passive"))
      (node (ref "C6") (pin "2") (pinfunction "2_2") (pintype "passive"))
      (node (ref "C7") (pin "2") (pinfunction "2_2") (pintype "passive"))
      (node (ref "C8") (pin "2") (pinfunction "2_2") (pintype "passive"))
      (node (ref "ISP1") (pin "2") (pinfunction "2_2") (pintype "passive"))
      (node (ref "LED0") (pin "1") (pinfunction "1_1") (pintype "passive"))
      (node (ref "LED1") (pin "1") (pinfunction "1_1") (pintype "passive"))
      (node (ref "LED2") (pin "1") (pinfunction "1_1") (pintype "passive"))
      (node (ref "LED3") (pin "1") (pinfunction "1_1") (pintype "passive"))
      (node (ref "LED4") (pin "1") (pinfunction "1_1") (pintype "passive"))
      (node (ref "LED5") (pin "1") (pinfunction "1_1") (pintype "passive"))
      (node (ref "LED6") (pin "1") (pinfunction "1_1") (pintype "passive"))
      (node (ref "LED7") (pin "1") (pinfunction "1_1") (pintype "passive"))
      (node (ref "P1") (pin "18") (pinfunction "18_18") (pintype "passive"))
      (node (ref "P2") (pin "17") (pinfunction "17_17") (pintype "passive"))
      (node (ref "P5") (pin "2") (pinfunction "2_2") (pintype "passive"))
      (node (ref "P9") (pin "3") (pinfunction "3_3") (pintype "passive"))
      (node (ref "R1") (pin "2") (pinfunction "2_2") (pintype "passive"))
      (node (ref "R19") (pin "1") (pinfunction "1_1") (pintype "passive"))
      (node (ref "R2") (pin "1") (pinfunction "1_1") (pintype "passive"))
      (node (ref "R20") (pin "1") (pinfunction "1_1") (pintype "passive"))
      (node (ref "R21") (pin "1") (pinfunction "1_1") (pintype "passive"))
      (node (ref "R22") (pin "1") (pinfunction "1_1") (pintype "passive"))
      (node (ref "R37") (pin "1") (pinfunction "1_1") (pintype "passive"))
      (node (ref "U1") (pin "17") (pinfunction "VCC_17") (pintype "power_in"))
      (node (ref "U1") (pin "27") (pinfunction "AVCC_27") (pintype "power_in"))
      (node (ref "U1") (pin "29") (pinfunction "AREF_29") (pintype "passive"))
      (node (ref "U1") (pin "38") (pinfunction "VCC_38") (pintype "power_in"))
      (node (ref "U1") (pin "5") (pinfunction "VCC_5") (pintype "power_in"))
      (node (ref "U2") (pin "10") (pinfunction "RST_10") (pintype "passive"))
      (node (ref "U2") (pin "16") (pinfunction "VCC_16") (pintype "passive"))
      (node (ref "U3") (pin "10") (pinfunction "RST_10") (pintype "passive"))
      (node (ref "U3") (pin "16") (pinfunction "VCC_16") (pintype "passive"))
      (node (ref "U5") (pin "1") (pinfunction "VCC2_1") (pintype "passive"))
    )
    (net (code "103") (name "VCC_S") (class "Default")
      (node (ref "C14") (pin "1") (pinfunction "1_1") (pintype "passive"))
      (node (ref "C17") (pin "1") (pinfunction "1_1") (pintype "passive"))
      (node (ref "P5") (pin "1") (pinfunction "1_1") (pintype "passive"))
      (node (ref "R34") (pin "1") (pinfunction "1_1") (pintype "passive"))
      (node (ref "R36") (pin "1") (pinfunction "1_1") (pintype "passive"))
      (node (ref "U6") (pin "19") (pinfunction "RESET_19") (pintype "passive"))
      (node (ref "U6") (pin "20") (pinfunction "VDD_20") (pintype "passive"))
      (node (ref "U6") (pin "24") (pinfunction "VDD_PLL_24") (pintype "passive"))
      (node (ref "U6") (pin "4") (pinfunction "VDD_232_4") (pintype "passive"))
      (node (ref "U6") (pin "8") (pinfunction "VDD_8") (pintype "passive"))
    )
    (net (code "104") (name "unconnected-(ISP1-Pad3)") (class "Default")
      (node (ref "ISP1") (pin "3") (pinfunction "3_3") (pintype "passive"))
    )
    (net (code "105") (name "unconnected-(ISP1-Pad4)") (class "Default")
      (node (ref "ISP1") (pin "4") (pinfunction "4_4") (pintype "passive"))
    )
    (net (code "106") (name "unconnected-(ISP1-Pad6)") (class "Default")
      (node (ref "ISP1") (pin "6") (pinfunction "6_6") (pintype "passive"))
    )
    (net (code "107") (name "unconnected-(ISP1-Pad8)") (class "Default")
      (node (ref "ISP1") (pin "8") (pinfunction "8_8") (pintype "passive"))
    )
    (net (code "108") (name "unconnected-(P5-Pad3)") (class "Default")
      (node (ref "P5") (pin "3") (pinfunction "3_3") (pintype "passive"))
    )
    (net (code "109") (name "unconnected-(PAD1-0-Pad1)") (class "Default")
      (node (ref "PAD1") (pin "1") (pinfunction "0_1") (pintype "passive"))
    )
    (net (code "110") (name "unconnected-(PAD1-1-Pad2)") (class "Default")
      (node (ref "PAD1") (pin "2") (pinfunction "1_2") (pintype "passive"))
    )
    (net (code "111") (name "unconnected-(PAD1-2-Pad3)") (class "Default")
      (node (ref "PAD1") (pin "3") (pinfunction "2_3") (pintype "passive"))
    )
    (net (code "112") (name "unconnected-(PAD1-3-Pad4)") (class "Default")
      (node (ref "PAD1") (pin "4") (pinfunction "3_4") (pintype "passive"))
    )
    (net (code "113") (name "unconnected-(PAD2-0-Pad1)") (class "Default")
      (node (ref "PAD2") (pin "1") (pinfunction "0_1") (pintype "passive"))
    )
    (net (code "114") (name "unconnected-(PAD2-1-Pad2)") (class "Default")
      (node (ref "PAD2") (pin "2") (pinfunction "1_2") (pintype "passive"))
    )
    (net (code "115") (name "unconnected-(PAD2-2-Pad3)") (class "Default")
      (node (ref "PAD2") (pin "3") (pinfunction "2_3") (pintype "passive"))
    )
    (net (code "116") (name "unconnected-(PAD2-3-Pad4)") (class "Default")
      (node (ref "PAD2") (pin "4") (pinfunction "3_4") (pintype "passive"))
    )
    (net (code "117") (name "unconnected-(PAD3-0-Pad1)") (class "Default")
      (node (ref "PAD3") (pin "1") (pinfunction "0_1") (pintype "passive"))
    )
    (net (code "118") (name "unconnected-(PAD3-1-Pad2)") (class "Default")
      (node (ref "PAD3") (pin "2") (pinfunction "1_2") (pintype "passive"))
    )
    (net (code "119") (name "unconnected-(PAD3-2-Pad3)") (class "Default")
      (node (ref "PAD3") (pin "3") (pinfunction "2_3") (pintype "passive"))
    )
    (net (code "120") (name "unconnected-(PAD3-3-Pad4)") (class "Default")
      (node (ref "PAD3") (pin "4") (pinfunction "3_4") (pintype "passive"))
    )
    (net (code "121") (name "unconnected-(PAD4-0-Pad1)") (class "Default")
      (node (ref "PAD4") (pin "1") (pinfunction "0_1") (pintype "passive"))
    )
    (net (code "122") (name "unconnected-(PAD4-1-Pad2)") (class "Default")
      (node (ref "PAD4") (pin "2") (pinfunction "1_2") (pintype "passive"))
    )
    (net (code "123") (name "unconnected-(PAD4-2-Pad3)") (class "Default")
      (node (ref "PAD4") (pin "3") (pinfunction "2_3") (pintype "passive"))
    )
    (net (code "124") (name "unconnected-(PAD4-3-Pad4)") (class "Default")
      (node (ref "PAD4") (pin "4") (pinfunction "3_4") (pintype "passive"))
    )
    (net (code "125") (name "unconnected-(U3-SQh-Pad9)") (class "Default")
      (node (ref "U3") (pin "9") (pinfunction "SQh_9") (pintype "passive"))
    )
    (net (code "126") (name "unconnected-(U6-CTS_N-Pad11)") (class "Default")
      (node (ref "U6") (pin "11") (pinfunction "CTS_N_11") (pintype "passive+no_connect"))
    )
    (net (code "127") (name "unconnected-(U6-DCD_N-Pad10)") (class "Default")
      (node (ref "U6") (pin "10") (pinfunction "DCD_N_10") (pintype "passive+no_connect"))
    )
    (net (code "128") (name "unconnected-(U6-DSR_N-Pad9)") (class "Default")
      (node (ref "U6") (pin "9") (pinfunction "DSR_N_9") (pintype "passive+no_connect"))
    )
    (net (code "129") (name "unconnected-(U6-DTR_N-Pad2)") (class "Default")
      (node (ref "U6") (pin "2") (pinfunction "DTR_N_2") (pintype "passive+no_connect"))
    )
    (net (code "130") (name "unconnected-(U6-EE_CLK-Pad13)") (class "Default")
      (node (ref "U6") (pin "13") (pinfunction "EE_CLK_13") (pintype "passive+no_connect"))
    )
    (net (code "131") (name "unconnected-(U6-EE_DATA-Pad14)") (class "Default")
      (node (ref "U6") (pin "14") (pinfunction "EE_DATA_14") (pintype "passive+no_connect"))
    )
    (net (code "132") (name "unconnected-(U6-RI_N-Pad6)") (class "Default")
      (node (ref "U6") (pin "6") (pinfunction "RI_N_6") (pintype "passive+no_connect"))
    )
    (net (code "133") (name "unconnected-(U6-RTS_N-Pad3)") (class "Default")
      (node (ref "U6") (pin "3") (pinfunction "RTS_N_3") (pintype "passive+no_connect"))
    )
    (net (code "134") (name "unconnected-(U6-SHTD_N-Pad12)") (class "Default")
      (node (ref "U6") (pin "12") (pinfunction "SHTD_N_12") (pintype "passive+no_connect"))
    )
  )
)
